# power_supply.net
KiCad netlist of a schematic drawn in EAGLE
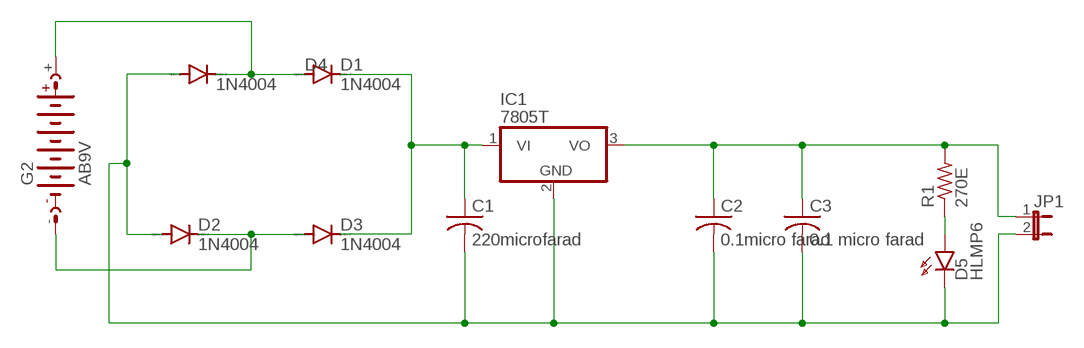
[diagram p0: schematic, sheet 1]

(export (version "E")
  (design (tool "Eeschema 10.0.6"))
  (components
    (comp (ref "C1")
      (value "220microfarad")
      (footprint "eagle-import:C050-030X075")
      (libsource (lib "eagle-import") (part "C-US050-030X075"))
    )
    (comp (ref "C2")
      (value "0.1micro farad")
      (footprint "eagle-import:C050-030X075")
      (libsource (lib "eagle-import") (part "C-US050-030X075"))
    )
    (comp (ref "C3")
      (value "0.1 micro farad")
      (footprint "eagle-import:C050-030X075")
      (libsource (lib "eagle-import") (part "C-US050-030X075"))
    )
    (comp (ref "D1")
      (value "1N4004")
      (footprint "eagle-import:DO41-10")
      (libsource (lib "eagle-import") (part "1N4004"))
    )
    (comp (ref "D2")
      (value "1N4004")
      (footprint "eagle-import:DO41-10")
      (libsource (lib "eagle-import") (part "1N4004"))
    )
    (comp (ref "D3")
      (value "1N4004")
      (footprint "eagle-import:DO41-10")
      (libsource (lib "eagle-import") (part "1N4004"))
    )
    (comp (ref "D4")
      (value "1N4004")
      (footprint "eagle-import:DO41-10")
      (libsource (lib "eagle-import") (part "1N4004"))
    )
    (comp (ref "D5")
      (value "HLMP6")
      (footprint "eagle-import:HLMP6")
      (fields (field (name "MF") "AGILENT TECHNOLOGIES") (field (name "MPN") "HLMP-6500"))
      (libsource (lib "eagle-import") (part "HLMP6"))
    )
    (comp (ref "G2")
      (value "AB9V")
      (footprint "eagle-import:AB9V")
      (libsource (lib "eagle-import") (part "AB9V"))
    )
    (comp (ref "IC1")
      (value "7805T")
      (footprint "eagle-import:TO220H")
      (libsource (lib "eagle-import") (part "78T05"))
    )
    (comp (ref "JP1")
      (value "JP1E")
      (footprint "eagle-import:JP1")
      (libsource (lib "eagle-import") (part "JP1E"))
    )
    (comp (ref "R1")
      (value "270E")
      (footprint "eagle-import:0204_7")
      (libsource (lib "eagle-import") (part "R-US_0204/7"))
    )
  )
  (nets
    (net (code "1") (name "Net-(D1-PadA)") (class "Default")
      (node (ref "D1") (pin "A") (pinfunction "A_A") (pintype "passive"))
      (node (ref "D4") (pin "C") (pinfunction "C_C") (pintype "passive"))
      (node (ref "G2") (pin "+") (pinfunction "+_+") (pintype "passive"))
    )
    (net (code "2") (name "Net-(D2-PadC)") (class "Default")
      (node (ref "D2") (pin "C") (pinfunction "C_C") (pintype "passive"))
      (node (ref "D3") (pin "A") (pinfunction "A_A") (pintype "passive"))
      (node (ref "G2") (pin "-") (pinfunction "-_-") (pintype "passive"))
    )
    (net (code "3") (name "Net-(D5-PadA)") (class "Default")
      (node (ref "D5") (pin "A") (pinfunction "A_A") (pintype "passive"))
      (node (ref "R1") (pin "1") (pinfunction "1_1") (pintype "passive"))
    )
    (net (code "4") (name "Net-(IC1-GND)") (class "Default")
      (node (ref "C1") (pin "2") (pinfunction "2_2") (pintype "passive"))
      (node (ref "C2") (pin "2") (pinfunction "2_2") (pintype "passive"))
      (node (ref "C3") (pin "2") (pinfunction "2_2") (pintype "passive"))
      (node (ref "D2") (pin "A") (pinfunction "A_A") (pintype "passive"))
      (node (ref "D4") (pin "A") (pinfunction "A_A") (pintype "passive"))
      (node (ref "D5") (pin "K") (pinfunction "K_K") (pintype "passive"))
      (node (ref "IC1") (pin "2") (pinfunction "GND_2") (pintype "passive"))
      (node (ref "JP1") (pin "2") (pinfunction "2_2") (pintype "passive"))
    )
    (net (code "5") (name "Net-(IC1-VI)") (class "Default")
      (node (ref "C1") (pin "1") (pinfunction "1_1") (pintype "passive"))
      (node (ref "D1") (pin "C") (pinfunction "C_C") (pintype "passive"))
      (node (ref "D3") (pin "C") (pinfunction "C_C") (pintype "passive"))
      (node (ref "IC1") (pin "1") (pinfunction "VI_1") (pintype "input"))
    )
    (net (code "6") (name "Net-(IC1-VO)") (class "Default")
      (node (ref "C2") (pin "1") (pinfunction "1_1") (pintype "passive"))
      (node (ref "C3") (pin "1") (pinfunction "1_1") (pintype "passive"))
      (node (ref "IC1") (pin "3") (pinfunction "VO_3") (pintype "passive"))
      (node (ref "JP1") (pin "1") (pinfunction "1_1") (pintype "passive"))
      (node (ref "R1") (pin "2") (pinfunction "2_2") (pintype "passive"))
    )
  )
)
